# easyeda-schematics.net
KiCad netlist of a schematic drawn in EasyEDA
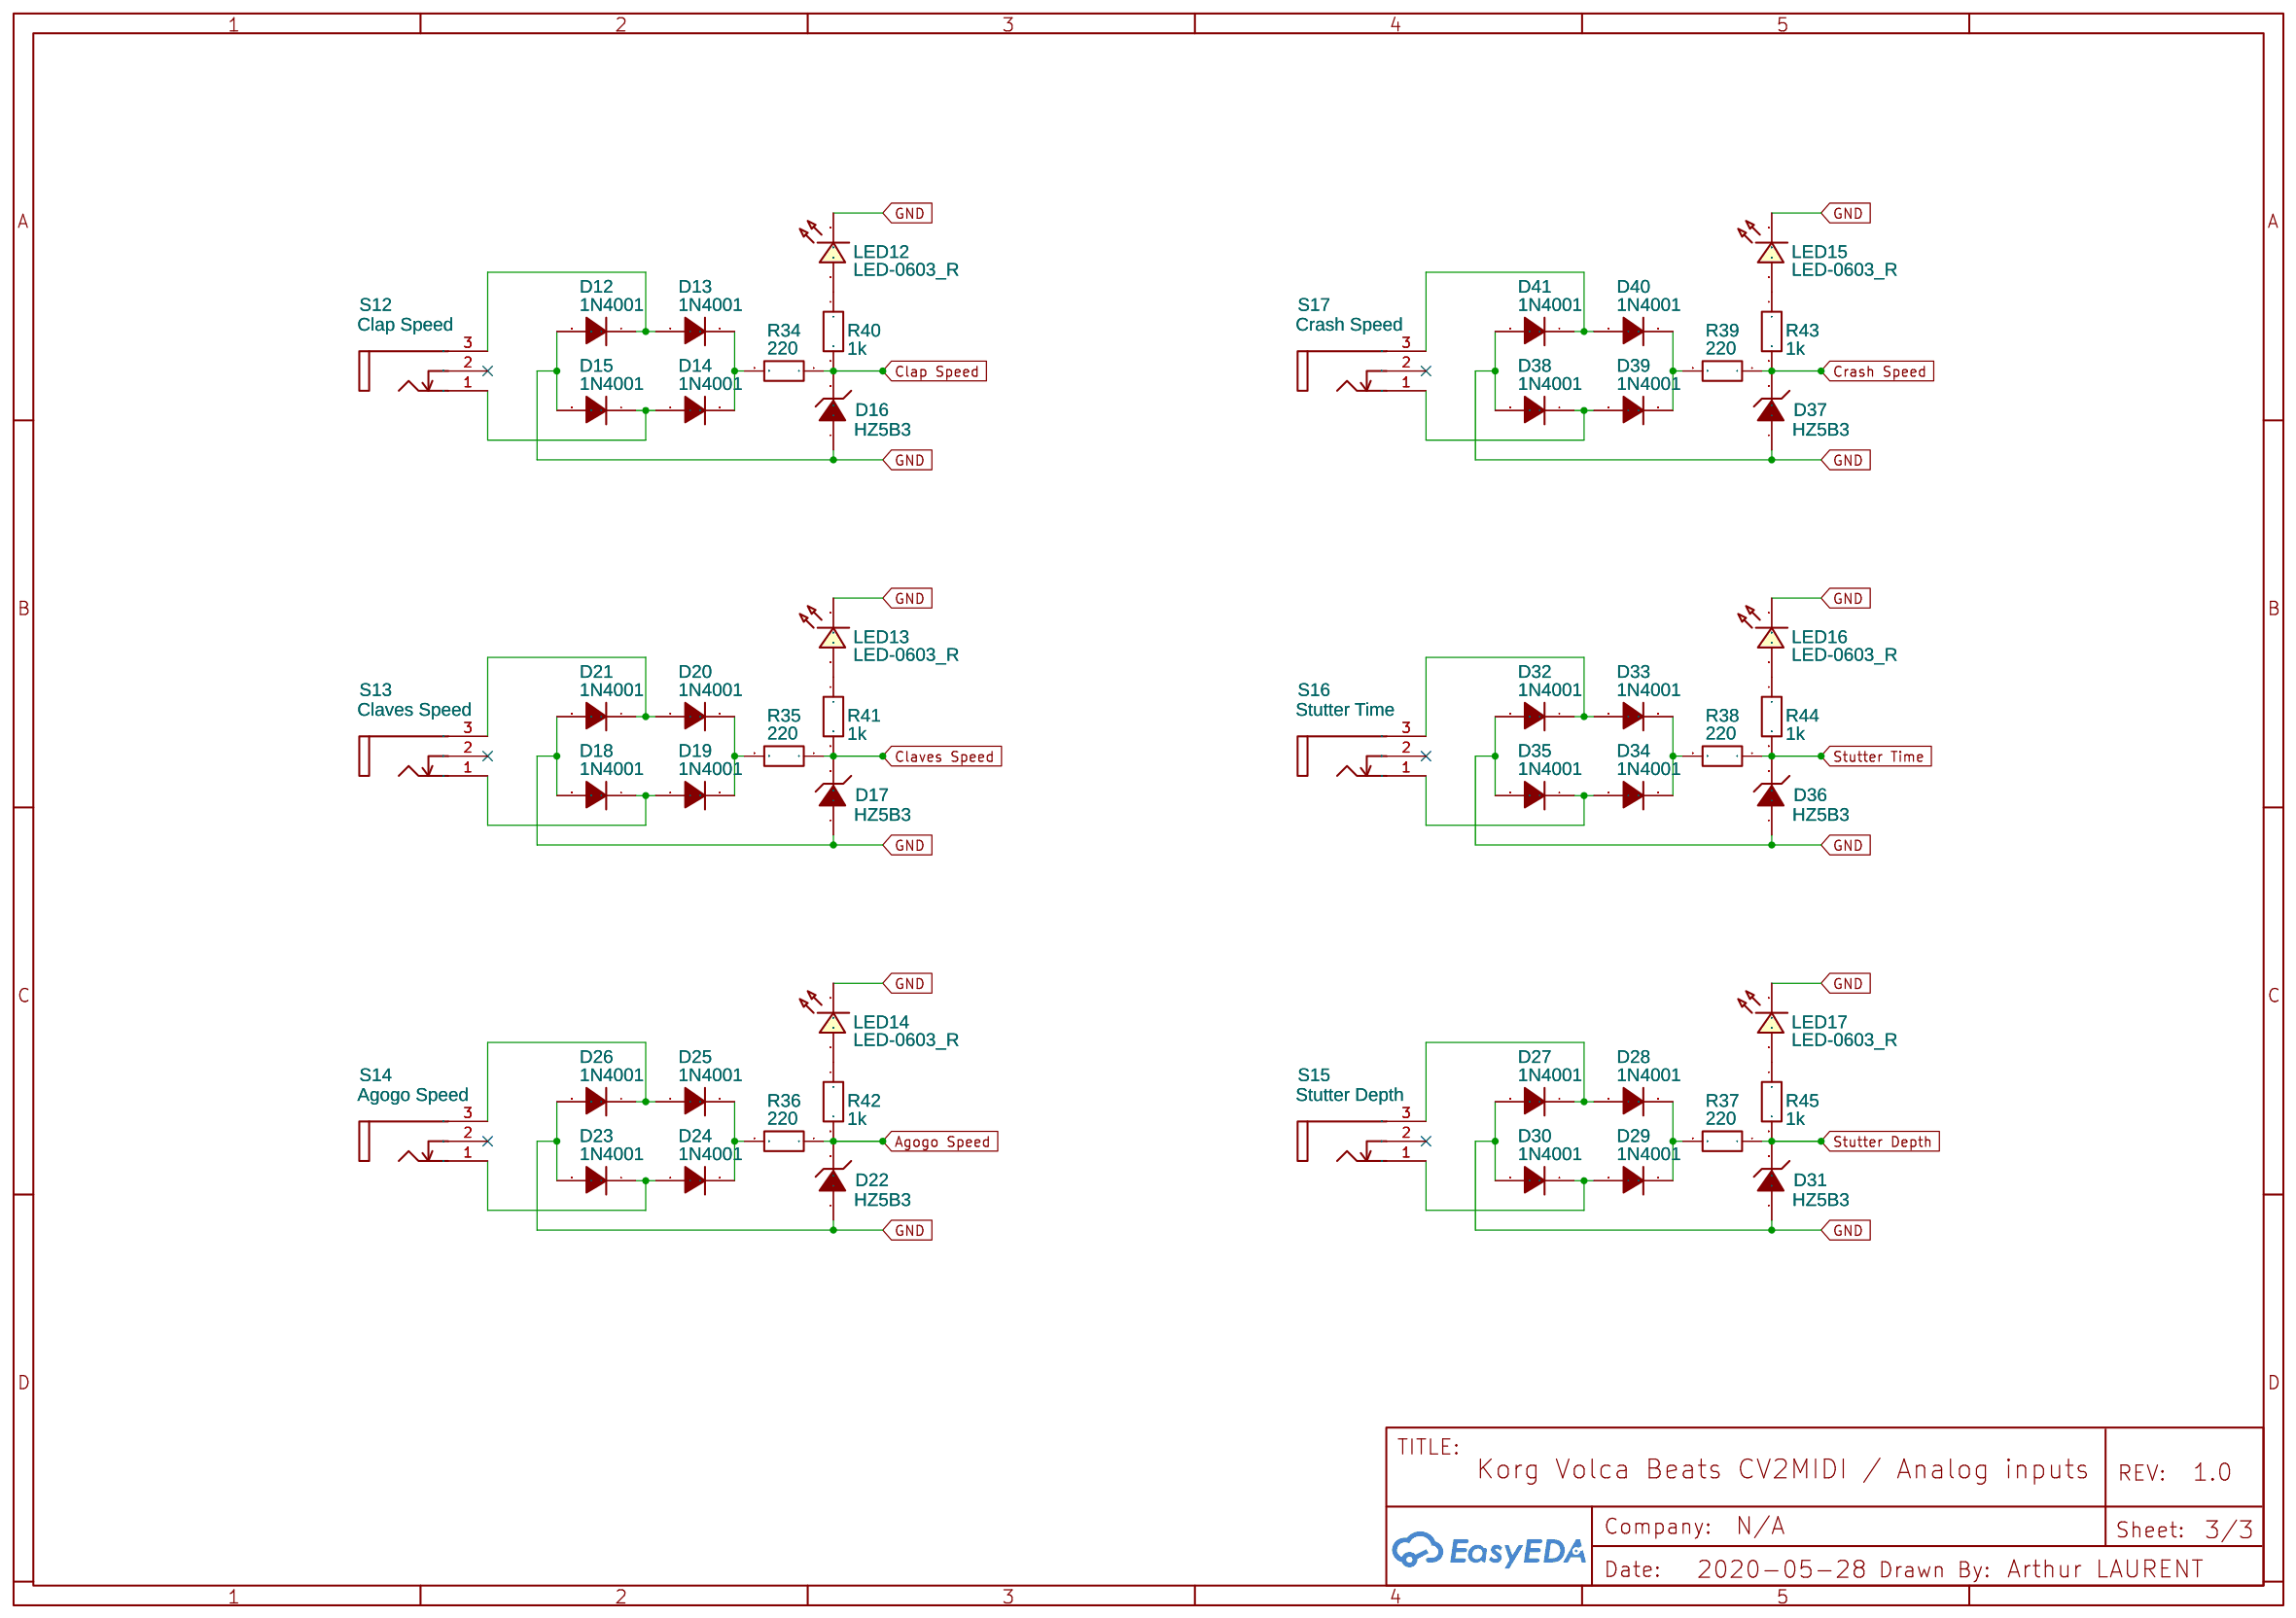
[diagram p0: Digital Inputs]
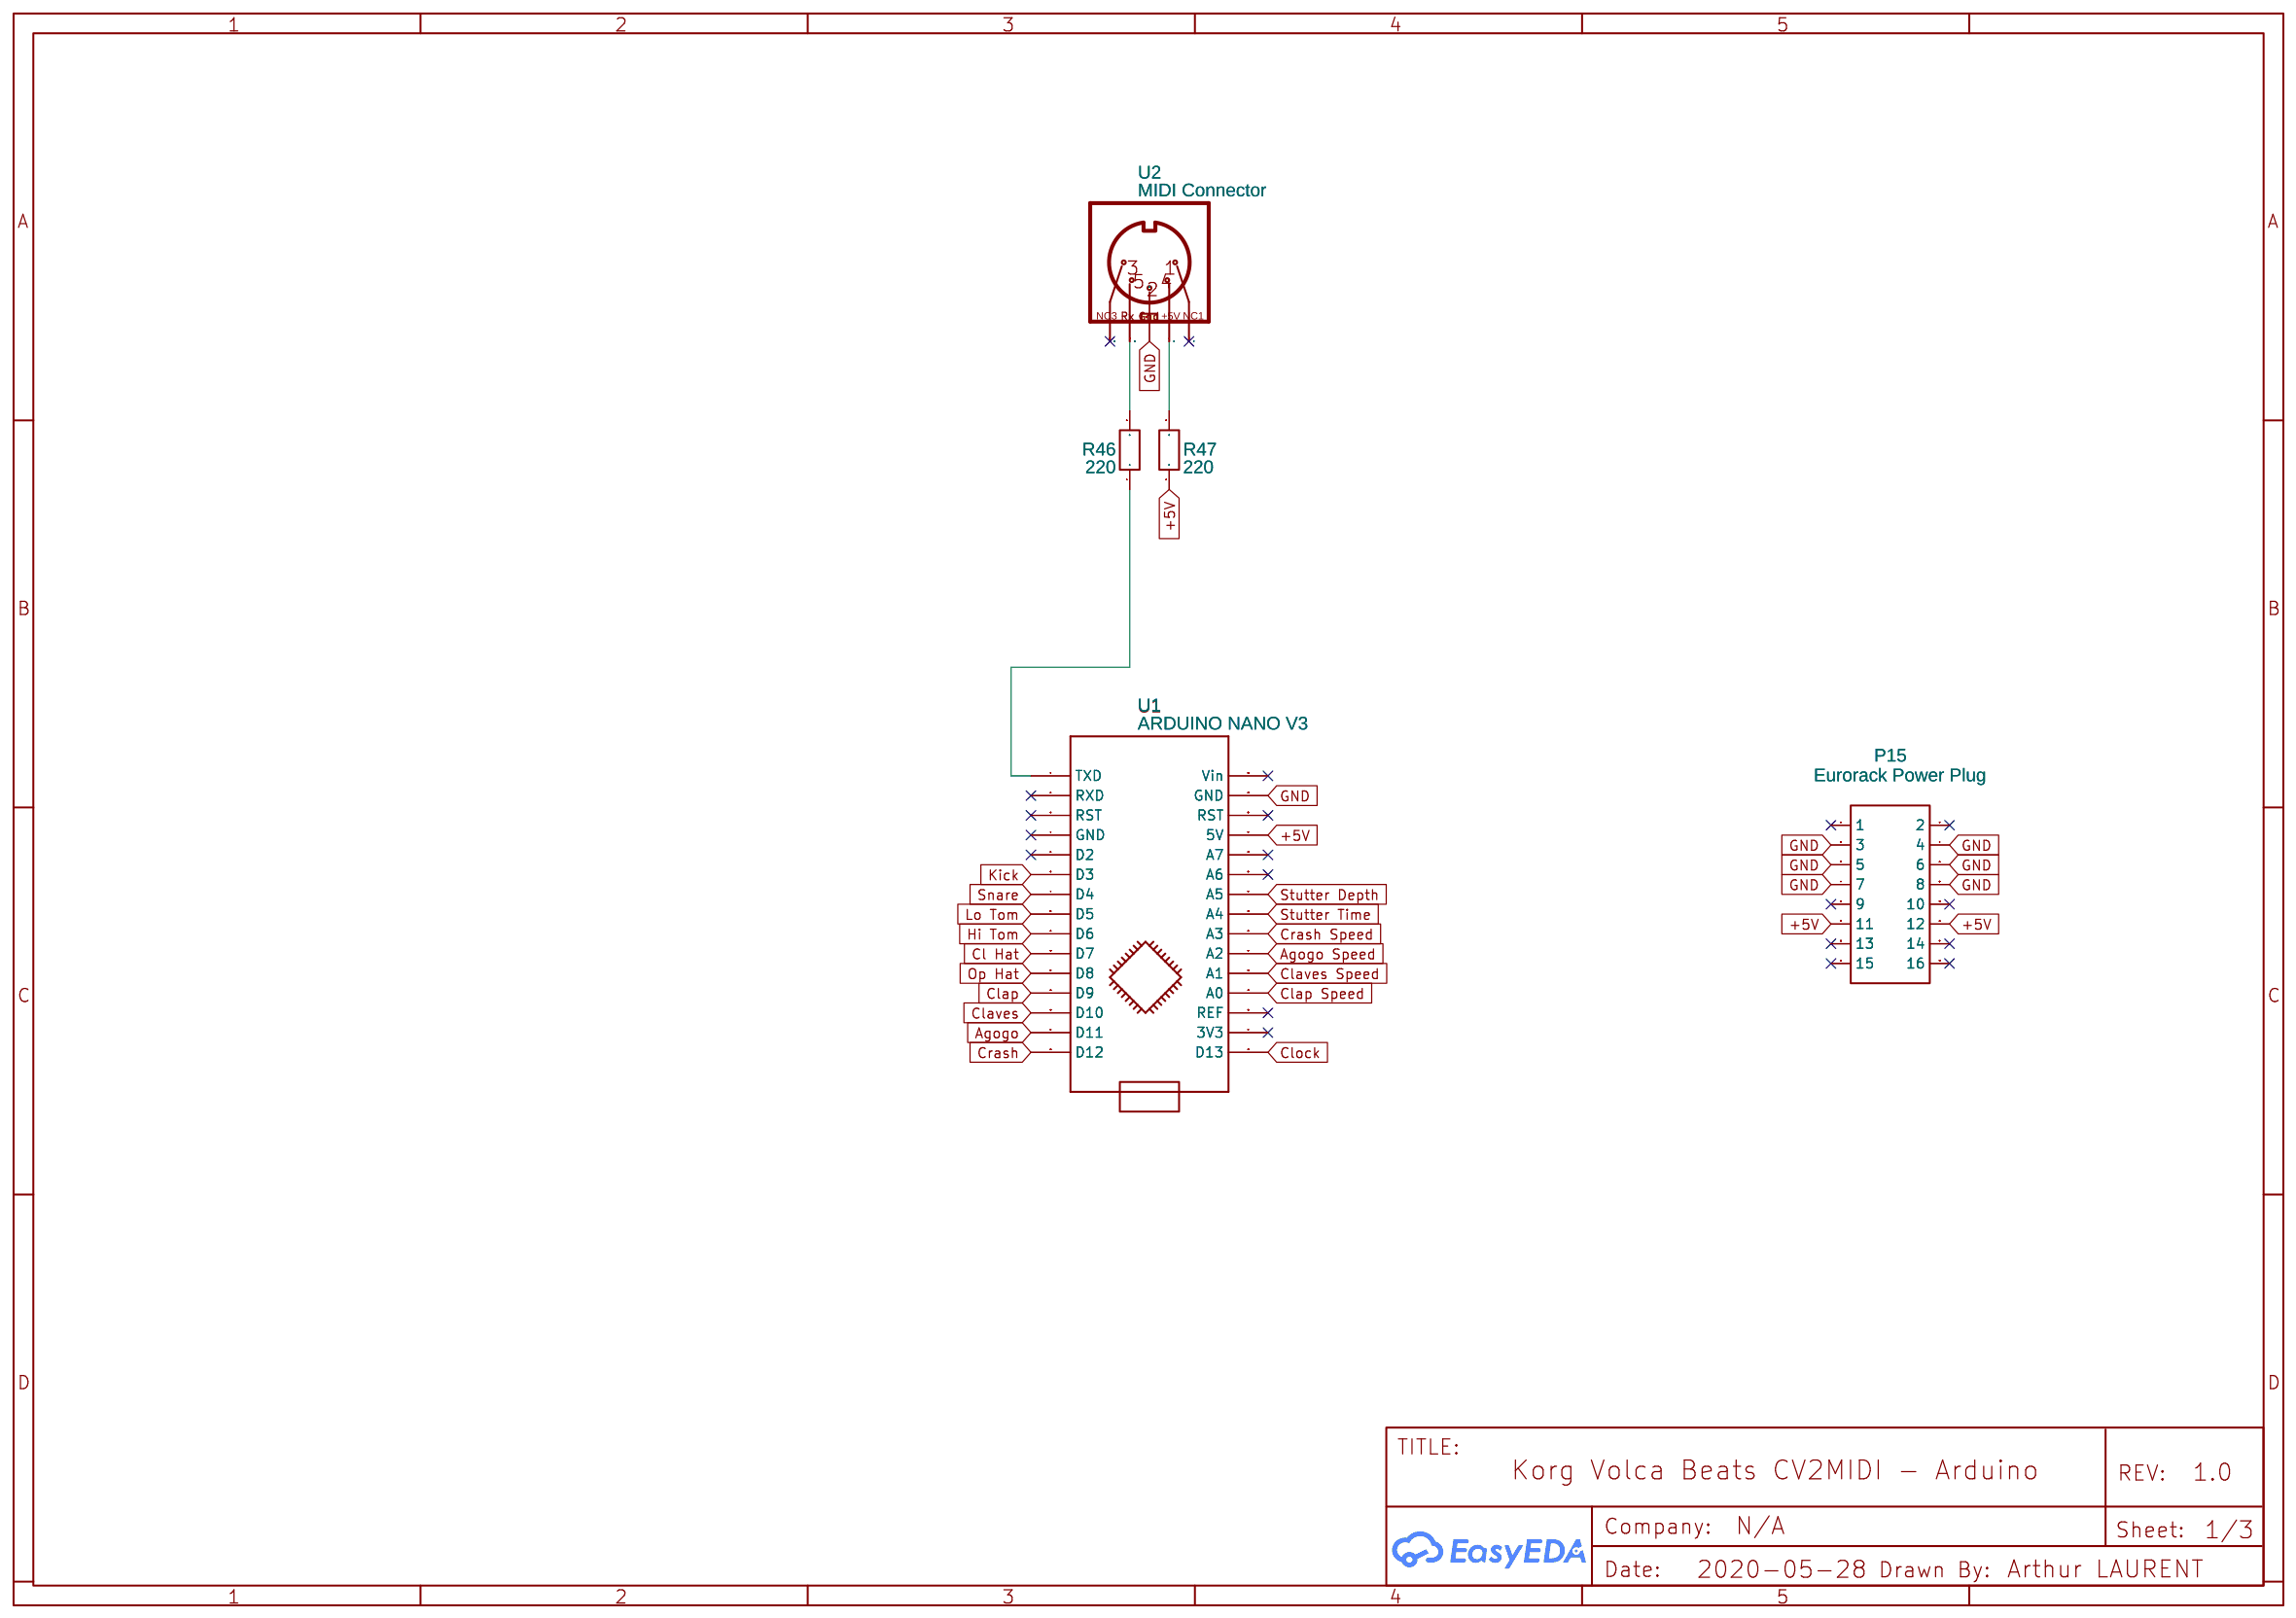
[diagram p1: Arduino]
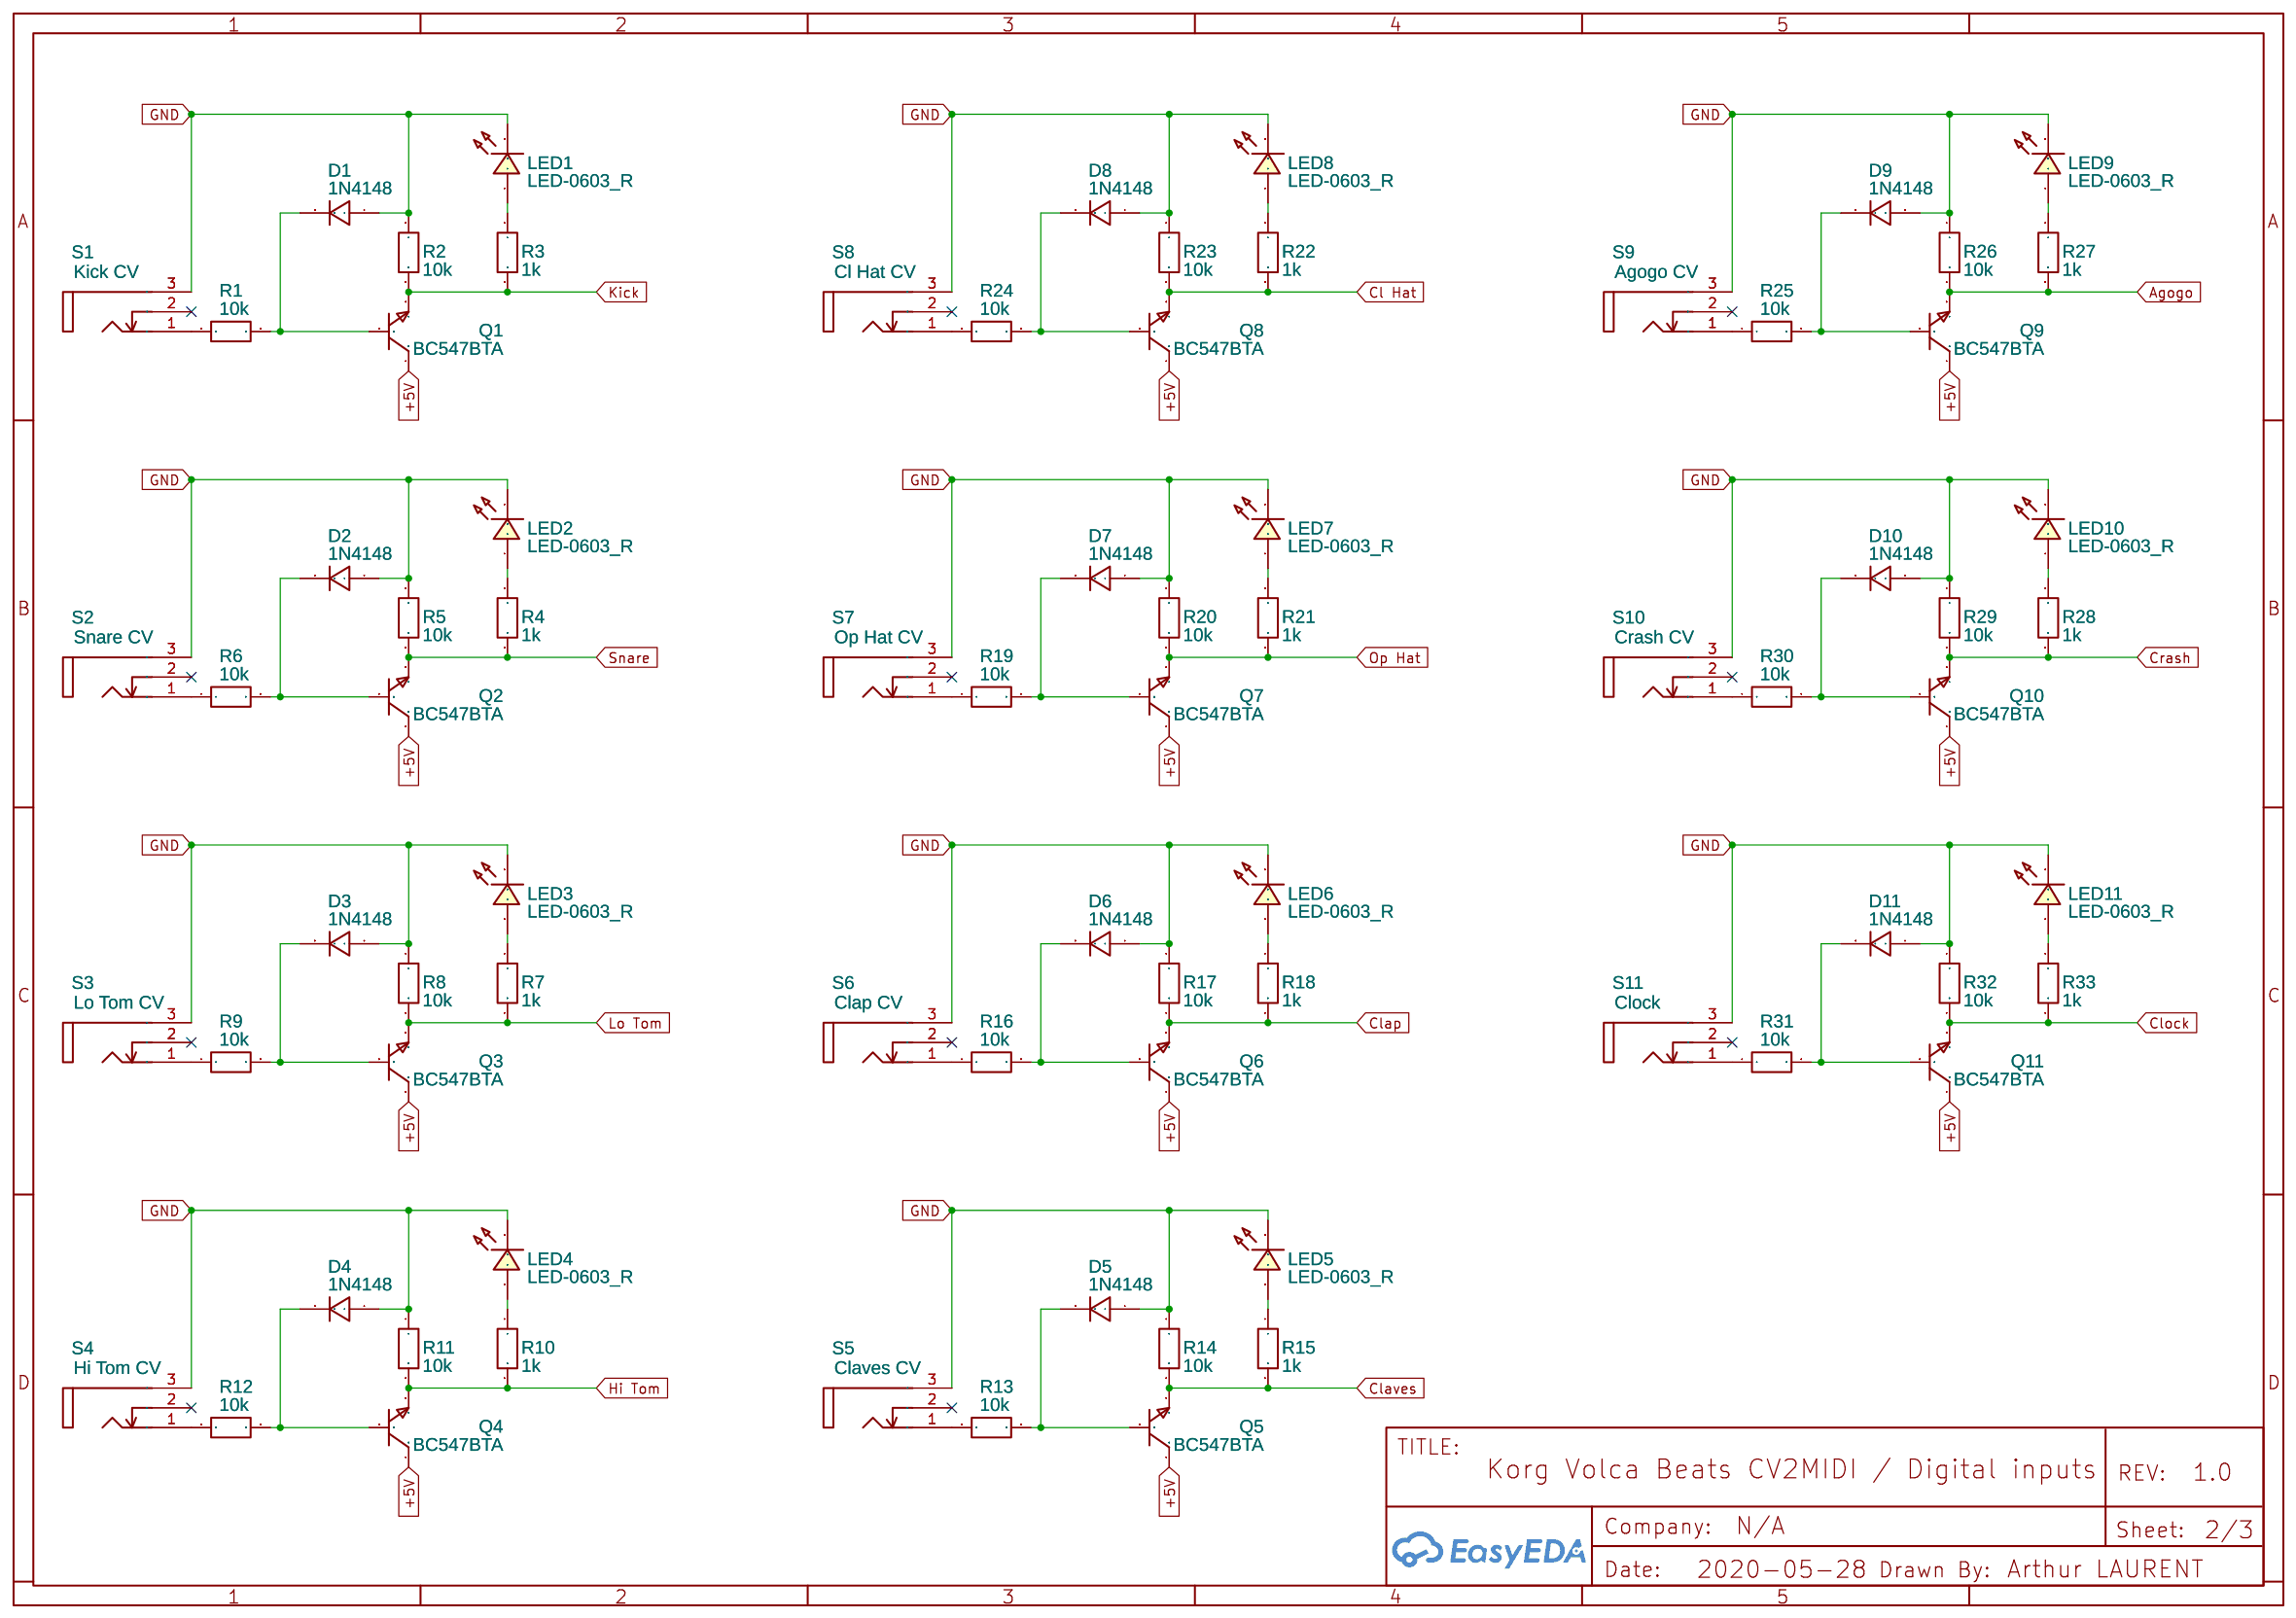
[diagram p2: Analog Inputs]

(export (version "E")
  (design (tool "Eeschema 10.0.6"))
  (components
    (comp (ref "D12")
      (value "1N4001")
      (fields (field (name "BOM_Supplier Part") "C82804"))
      (libsource (lib "") (part "1N4001"))
    )
    (comp (ref "D13")
      (value "1N4001")
      (fields (field (name "BOM_Supplier Part") "C82804"))
      (libsource (lib "") (part "1N4001"))
    )
    (comp (ref "D14")
      (value "1N4001")
      (fields (field (name "BOM_Supplier Part") "C82804"))
      (libsource (lib "") (part "1N4001"))
    )
    (comp (ref "D15")
      (value "1N4001")
      (fields (field (name "BOM_Supplier Part") "C82804"))
      (libsource (lib "") (part "1N4001"))
    )
    (comp (ref "D16")
      (value "HZ5B3")
      (fields (field (name "BOM_Supplier Part") "C45643"))
      (libsource (lib "") (part "HZ5B3"))
    )
    (comp (ref "D17")
      (value "HZ5B3")
      (fields (field (name "BOM_Supplier Part") "C45643"))
      (libsource (lib "") (part "HZ5B3"))
    )
    (comp (ref "D18")
      (value "1N4001")
      (fields (field (name "BOM_Supplier Part") "C82804"))
      (libsource (lib "") (part "1N4001"))
    )
    (comp (ref "D19")
      (value "1N4001")
      (fields (field (name "BOM_Supplier Part") "C82804"))
      (libsource (lib "") (part "1N4001"))
    )
    (comp (ref "D20")
      (value "1N4001")
      (fields (field (name "BOM_Supplier Part") "C82804"))
      (libsource (lib "") (part "1N4001"))
    )
    (comp (ref "D21")
      (value "1N4001")
      (fields (field (name "BOM_Supplier Part") "C82804"))
      (libsource (lib "") (part "1N4001"))
    )
    (comp (ref "D22")
      (value "HZ5B3")
      (fields (field (name "BOM_Supplier Part") "C45643"))
      (libsource (lib "") (part "HZ5B3"))
    )
    (comp (ref "D23")
      (value "1N4001")
      (fields (field (name "BOM_Supplier Part") "C82804"))
      (libsource (lib "") (part "1N4001"))
    )
    (comp (ref "D24")
      (value "1N4001")
      (fields (field (name "BOM_Supplier Part") "C82804"))
      (libsource (lib "") (part "1N4001"))
    )
    (comp (ref "D25")
      (value "1N4001")
      (fields (field (name "BOM_Supplier Part") "C82804"))
      (libsource (lib "") (part "1N4001"))
    )
    (comp (ref "D26")
      (value "1N4001")
      (fields (field (name "BOM_Supplier Part") "C82804"))
      (libsource (lib "") (part "1N4001"))
    )
    (comp (ref "D27")
      (value "1N4001")
      (fields (field (name "BOM_Supplier Part") "C82804"))
      (libsource (lib "") (part "1N4001"))
    )
    (comp (ref "D28")
      (value "1N4001")
      (fields (field (name "BOM_Supplier Part") "C82804"))
      (libsource (lib "") (part "1N4001"))
    )
    (comp (ref "D29")
      (value "1N4001")
      (fields (field (name "BOM_Supplier Part") "C82804"))
      (libsource (lib "") (part "1N4001"))
    )
    (comp (ref "D30")
      (value "1N4001")
      (fields (field (name "BOM_Supplier Part") "C82804"))
      (libsource (lib "") (part "1N4001"))
    )
    (comp (ref "D31")
      (value "HZ5B3")
      (fields (field (name "BOM_Supplier Part") "C45643"))
      (libsource (lib "") (part "HZ5B3"))
    )
    (comp (ref "D32")
      (value "1N4001")
      (fields (field (name "BOM_Supplier Part") "C82804"))
      (libsource (lib "") (part "1N4001"))
    )
    (comp (ref "D33")
      (value "1N4001")
      (fields (field (name "BOM_Supplier Part") "C82804"))
      (libsource (lib "") (part "1N4001"))
    )
    (comp (ref "D34")
      (value "1N4001")
      (fields (field (name "BOM_Supplier Part") "C82804"))
      (libsource (lib "") (part "1N4001"))
    )
    (comp (ref "D35")
      (value "1N4001")
      (fields (field (name "BOM_Supplier Part") "C82804"))
      (libsource (lib "") (part "1N4001"))
    )
    (comp (ref "D36")
      (value "HZ5B3")
      (fields (field (name "BOM_Supplier Part") "C45643"))
      (libsource (lib "") (part "HZ5B3"))
    )
    (comp (ref "D37")
      (value "HZ5B3")
      (fields (field (name "BOM_Supplier Part") "C45643"))
      (libsource (lib "") (part "HZ5B3"))
    )
    (comp (ref "D38")
      (value "1N4001")
      (fields (field (name "BOM_Supplier Part") "C82804"))
      (libsource (lib "") (part "1N4001"))
    )
    (comp (ref "D39")
      (value "1N4001")
      (fields (field (name "BOM_Supplier Part") "C82804"))
      (libsource (lib "") (part "1N4001"))
    )
    (comp (ref "D40")
      (value "1N4001")
      (fields (field (name "BOM_Supplier Part") "C82804"))
      (libsource (lib "") (part "1N4001"))
    )
    (comp (ref "D41")
      (value "1N4001")
      (fields (field (name "BOM_Supplier Part") "C82804"))
      (libsource (lib "") (part "1N4001"))
    )
    (comp (ref "LED12")
      (value "LED-0603_R")
      (fields
        (field (name "BOM_Manufacturer Part") "19-217/R6C-AL1M2VY/3T")
        (field (name "BOM_Supplier Part") "C72044")
      )
      (libsource (lib "") (part "LED-0603_R"))
    )
    (comp (ref "LED13")
      (value "LED-0603_R")
      (fields
        (field (name "BOM_Manufacturer Part") "19-217/R6C-AL1M2VY/3T")
        (field (name "BOM_Supplier Part") "C72044")
      )
      (libsource (lib "") (part "LED-0603_R"))
    )
    (comp (ref "LED14")
      (value "LED-0603_R")
      (fields
        (field (name "BOM_Manufacturer Part") "19-217/R6C-AL1M2VY/3T")
        (field (name "BOM_Supplier Part") "C72044")
      )
      (libsource (lib "") (part "LED-0603_R"))
    )
    (comp (ref "LED15")
      (value "LED-0603_R")
      (fields
        (field (name "BOM_Manufacturer Part") "19-217/R6C-AL1M2VY/3T")
        (field (name "BOM_Supplier Part") "C72044")
      )
      (libsource (lib "") (part "LED-0603_R"))
    )
    (comp (ref "LED16")
      (value "LED-0603_R")
      (fields
        (field (name "BOM_Manufacturer Part") "19-217/R6C-AL1M2VY/3T")
        (field (name "BOM_Supplier Part") "C72044")
      )
      (libsource (lib "") (part "LED-0603_R"))
    )
    (comp (ref "LED17")
      (value "LED-0603_R")
      (fields
        (field (name "BOM_Manufacturer Part") "19-217/R6C-AL1M2VY/3T")
        (field (name "BOM_Supplier Part") "C72044")
      )
      (libsource (lib "") (part "LED-0603_R"))
    )
    (comp (ref "R34") (value "220") (libsource (lib "") (part "R_0201_EU_1")))
    (comp (ref "R35") (value "220") (libsource (lib "") (part "R_0201_EU_1")))
    (comp (ref "R36") (value "220") (libsource (lib "") (part "R_0201_EU_1")))
    (comp (ref "R37") (value "220") (libsource (lib "") (part "R_0201_EU_1")))
    (comp (ref "R38") (value "220") (libsource (lib "") (part "R_0201_EU_1")))
    (comp (ref "R39") (value "220") (libsource (lib "") (part "R_0201_EU_1")))
    (comp (ref "R40") (value "1k") (libsource (lib "") (part "R_0201_EU")))
    (comp (ref "R41") (value "1k") (libsource (lib "") (part "R_0201_EU")))
    (comp (ref "R42") (value "1k") (libsource (lib "") (part "R_0201_EU")))
    (comp (ref "R43") (value "1k") (libsource (lib "") (part "R_0201_EU")))
    (comp (ref "R44") (value "1k") (libsource (lib "") (part "R_0201_EU")))
    (comp (ref "R45") (value "1k") (libsource (lib "") (part "R_0201_EU")))
    (comp (ref "S12") (value "Clap Speed") (libsource (lib "") (part "3.5mm Jack Socket Mono")))
    (comp (ref "S13") (value "Claves Speed") (libsource (lib "") (part "3.5mm Jack Socket Mono")))
    (comp (ref "S14") (value "Agogo Speed") (libsource (lib "") (part "3.5mm Jack Socket Mono")))
    (comp (ref "S15") (value "Stutter Depth") (libsource (lib "") (part "3.5mm Jack Socket Mono")))
    (comp (ref "S16") (value "Stutter Time") (libsource (lib "") (part "3.5mm Jack Socket Mono")))
    (comp (ref "S17") (value "Crash Speed") (libsource (lib "") (part "3.5mm Jack Socket Mono")))
    (comp (ref "P15")
      (value "Eurorack Power Plug")
      (fields
        (field (name "BOM_Manufacturer Part") "IDC Box 2.54mm 16P　Straight")
        (field (name "BOM_Supplier Part") "C3406")
      )
      (libsource (lib "") (part "HDR-IDC-2.54-2X8P"))
    )
    (comp (ref "R46") (value "220") (libsource (lib "") (part "R_0201_EU")))
    (comp (ref "R47") (value "220") (libsource (lib "") (part "R_0201_EU")))
    (comp (ref "U1")
      (value "ARDUINO NANO V3")
      (fields (field (name "BOM_Manufacturer Part") "arduino_nano1"))
      (libsource (lib "") (part "ARDUINO NANO V3"))
    )
    (comp (ref "U2") (value "MIDI Connector") (libsource (lib "") (part "MIDI Connector")))
    (comp (ref "D1") (value "1N4148") (libsource (lib "") (part "1N4148")))
    (comp (ref "D2") (value "1N4148") (libsource (lib "") (part "1N4148")))
    (comp (ref "D3") (value "1N4148") (libsource (lib "") (part "1N4148")))
    (comp (ref "D4") (value "1N4148") (libsource (lib "") (part "1N4148")))
    (comp (ref "D5") (value "1N4148") (libsource (lib "") (part "1N4148")))
    (comp (ref "D6") (value "1N4148") (libsource (lib "") (part "1N4148")))
    (comp (ref "D7") (value "1N4148") (libsource (lib "") (part "1N4148")))
    (comp (ref "D8") (value "1N4148") (libsource (lib "") (part "1N4148")))
    (comp (ref "D9") (value "1N4148") (libsource (lib "") (part "1N4148")))
    (comp (ref "D10") (value "1N4148") (libsource (lib "") (part "1N4148")))
    (comp (ref "D11") (value "1N4148") (libsource (lib "") (part "1N4148")))
    (comp (ref "LED1")
      (value "LED-0603_R")
      (fields
        (field (name "BOM_Manufacturer Part") "19-217/R6C-AL1M2VY/3T")
        (field (name "BOM_Supplier Part") "C72044")
      )
      (libsource (lib "") (part "LED-0603_R"))
    )
    (comp (ref "LED2")
      (value "LED-0603_R")
      (fields
        (field (name "BOM_Manufacturer Part") "19-217/R6C-AL1M2VY/3T")
        (field (name "BOM_Supplier Part") "C72044")
      )
      (libsource (lib "") (part "LED-0603_R"))
    )
    (comp (ref "LED3")
      (value "LED-0603_R")
      (fields
        (field (name "BOM_Manufacturer Part") "19-217/R6C-AL1M2VY/3T")
        (field (name "BOM_Supplier Part") "C72044")
      )
      (libsource (lib "") (part "LED-0603_R"))
    )
    (comp (ref "LED4")
      (value "LED-0603_R")
      (fields
        (field (name "BOM_Manufacturer Part") "19-217/R6C-AL1M2VY/3T")
        (field (name "BOM_Supplier Part") "C72044")
      )
      (libsource (lib "") (part "LED-0603_R"))
    )
    (comp (ref "LED5")
      (value "LED-0603_R")
      (fields
        (field (name "BOM_Manufacturer Part") "19-217/R6C-AL1M2VY/3T")
        (field (name "BOM_Supplier Part") "C72044")
      )
      (libsource (lib "") (part "LED-0603_R"))
    )
    (comp (ref "LED6")
      (value "LED-0603_R")
      (fields
        (field (name "BOM_Manufacturer Part") "19-217/R6C-AL1M2VY/3T")
        (field (name "BOM_Supplier Part") "C72044")
      )
      (libsource (lib "") (part "LED-0603_R"))
    )
    (comp (ref "LED7")
      (value "LED-0603_R")
      (fields
        (field (name "BOM_Manufacturer Part") "19-217/R6C-AL1M2VY/3T")
        (field (name "BOM_Supplier Part") "C72044")
      )
      (libsource (lib "") (part "LED-0603_R"))
    )
    (comp (ref "LED8")
      (value "LED-0603_R")
      (fields
        (field (name "BOM_Manufacturer Part") "19-217/R6C-AL1M2VY/3T")
        (field (name "BOM_Supplier Part") "C72044")
      )
      (libsource (lib "") (part "LED-0603_R"))
    )
    (comp (ref "LED9")
      (value "LED-0603_R")
      (fields
        (field (name "BOM_Manufacturer Part") "19-217/R6C-AL1M2VY/3T")
        (field (name "BOM_Supplier Part") "C72044")
      )
      (libsource (lib "") (part "LED-0603_R"))
    )
    (comp (ref "LED10")
      (value "LED-0603_R")
      (fields
        (field (name "BOM_Manufacturer Part") "19-217/R6C-AL1M2VY/3T")
        (field (name "BOM_Supplier Part") "C72044")
      )
      (libsource (lib "") (part "LED-0603_R"))
    )
    (comp (ref "LED11")
      (value "LED-0603_R")
      (fields
        (field (name "BOM_Manufacturer Part") "19-217/R6C-AL1M2VY/3T")
        (field (name "BOM_Supplier Part") "C72044")
      )
      (libsource (lib "") (part "LED-0603_R"))
    )
    (comp (ref "Q1")
      (value "BC547BTA")
      (fields (field (name "BOM_Supplier Part") "C258144"))
      (libsource (lib "") (part "BC547BTA"))
    )
    (comp (ref "Q2")
      (value "BC547BTA")
      (fields (field (name "BOM_Supplier Part") "C258144"))
      (libsource (lib "") (part "BC547BTA"))
    )
    (comp (ref "Q3")
      (value "BC547BTA")
      (fields (field (name "BOM_Supplier Part") "C258144"))
      (libsource (lib "") (part "BC547BTA"))
    )
    (comp (ref "Q4")
      (value "BC547BTA")
      (fields (field (name "BOM_Supplier Part") "C258144"))
      (libsource (lib "") (part "BC547BTA"))
    )
    (comp (ref "Q5")
      (value "BC547BTA")
      (fields (field (name "BOM_Supplier Part") "C258144"))
      (libsource (lib "") (part "BC547BTA"))
    )
    (comp (ref "Q6")
      (value "BC547BTA")
      (fields (field (name "BOM_Supplier Part") "C258144"))
      (libsource (lib "") (part "BC547BTA"))
    )
    (comp (ref "Q7")
      (value "BC547BTA")
      (fields (field (name "BOM_Supplier Part") "C258144"))
      (libsource (lib "") (part "BC547BTA"))
    )
    (comp (ref "Q8")
      (value "BC547BTA")
      (fields (field (name "BOM_Supplier Part") "C258144"))
      (libsource (lib "") (part "BC547BTA"))
    )
    (comp (ref "Q9")
      (value "BC547BTA")
      (fields (field (name "BOM_Supplier Part") "C258144"))
      (libsource (lib "") (part "BC547BTA"))
    )
    (comp (ref "Q10")
      (value "BC547BTA")
      (fields (field (name "BOM_Supplier Part") "C258144"))
      (libsource (lib "") (part "BC547BTA"))
    )
    (comp (ref "Q11")
      (value "BC547BTA")
      (fields (field (name "BOM_Supplier Part") "C258144"))
      (libsource (lib "") (part "BC547BTA"))
    )
    (comp (ref "R1") (value "10k") (libsource (lib "") (part "R_0201_EU_1")))
    (comp (ref "R2") (value "10k") (libsource (lib "") (part "R_0201_EU")))
    (comp (ref "R3") (value "1k") (libsource (lib "") (part "R_0201_EU")))
    (comp (ref "R4") (value "1k") (libsource (lib "") (part "R_0201_EU")))
    (comp (ref "R5") (value "10k") (libsource (lib "") (part "R_0201_EU")))
    (comp (ref "R6") (value "10k") (libsource (lib "") (part "R_0201_EU_1")))
    (comp (ref "R7") (value "1k") (libsource (lib "") (part "R_0201_EU")))
    (comp (ref "R8") (value "10k") (libsource (lib "") (part "R_0201_EU")))
    (comp (ref "R9") (value "10k") (libsource (lib "") (part "R_0201_EU_1")))
    (comp (ref "R10") (value "1k") (libsource (lib "") (part "R_0201_EU")))
    (comp (ref "R11") (value "10k") (libsource (lib "") (part "R_0201_EU")))
    (comp (ref "R12") (value "10k") (libsource (lib "") (part "R_0201_EU_1")))
    (comp (ref "R13") (value "10k") (libsource (lib "") (part "R_0201_EU_1")))
    (comp (ref "R14") (value "10k") (libsource (lib "") (part "R_0201_EU")))
    (comp (ref "R15") (value "1k") (libsource (lib "") (part "R_0201_EU")))
    (comp (ref "R16") (value "10k") (libsource (lib "") (part "R_0201_EU_1")))
    (comp (ref "R17") (value "10k") (libsource (lib "") (part "R_0201_EU")))
    (comp (ref "R18") (value "1k") (libsource (lib "") (part "R_0201_EU")))
    (comp (ref "R19") (value "10k") (libsource (lib "") (part "R_0201_EU_1")))
    (comp (ref "R20") (value "10k") (libsource (lib "") (part "R_0201_EU")))
    (comp (ref "R21") (value "1k") (libsource (lib "") (part "R_0201_EU")))
    (comp (ref "R22") (value "1k") (libsource (lib "") (part "R_0201_EU")))
    (comp (ref "R23") (value "10k") (libsource (lib "") (part "R_0201_EU")))
    (comp (ref "R24") (value "10k") (libsource (lib "") (part "R_0201_EU_1")))
    (comp (ref "R25") (value "10k") (libsource (lib "") (part "R_0201_EU_1")))
    (comp (ref "R26") (value "10k") (libsource (lib "") (part "R_0201_EU")))
    (comp (ref "R27") (value "1k") (libsource (lib "") (part "R_0201_EU")))
    (comp (ref "R28") (value "1k") (libsource (lib "") (part "R_0201_EU")))
    (comp (ref "R29") (value "10k") (libsource (lib "") (part "R_0201_EU")))
    (comp (ref "R30") (value "10k") (libsource (lib "") (part "R_0201_EU_1")))
    (comp (ref "R31") (value "10k") (libsource (lib "") (part "R_0201_EU_1")))
    (comp (ref "R32") (value "10k") (libsource (lib "") (part "R_0201_EU")))
    (comp (ref "R33") (value "1k") (libsource (lib "") (part "R_0201_EU")))
    (comp (ref "S1") (value "Kick CV") (libsource (lib "") (part "3.5mm Jack Socket Mono")))
    (comp (ref "S2") (value "Snare CV") (libsource (lib "") (part "3.5mm Jack Socket Mono")))
    (comp (ref "S3") (value "Lo Tom CV") (libsource (lib "") (part "3.5mm Jack Socket Mono")))
    (comp (ref "S4") (value "Hi Tom CV") (libsource (lib "") (part "3.5mm Jack Socket Mono")))
    (comp (ref "S5") (value "Claves CV") (libsource (lib "") (part "3.5mm Jack Socket Mono")))
    (comp (ref "S6") (value "Clap CV") (libsource (lib "") (part "3.5mm Jack Socket Mono")))
    (comp (ref "S7") (value "Op Hat CV") (libsource (lib "") (part "3.5mm Jack Socket Mono")))
    (comp (ref "S8") (value "Cl Hat CV") (libsource (lib "") (part "3.5mm Jack Socket Mono")))
    (comp (ref "S9") (value "Agogo CV") (libsource (lib "") (part "3.5mm Jack Socket Mono")))
    (comp (ref "S10") (value "Crash CV") (libsource (lib "") (part "3.5mm Jack Socket Mono")))
    (comp (ref "S11") (value "Clock") (libsource (lib "") (part "3.5mm Jack Socket Mono")))
  )
  (nets
    (net (code "1") (name "+5V") (class "Default")
      (node (ref "P15") (pin "11") (pinfunction "11_11") (pintype "unspecified"))
      (node (ref "P15") (pin "12") (pinfunction "12_12") (pintype "unspecified"))
      (node (ref "Q1") (pin "1") (pinfunction "C_1") (pintype "unspecified"))
      (node (ref "Q10") (pin "1") (pinfunction "C_1") (pintype "unspecified"))
      (node (ref "Q11") (pin "1") (pinfunction "C_1") (pintype "unspecified"))
      (node (ref "Q2") (pin "1") (pinfunction "C_1") (pintype "unspecified"))
      (node (ref "Q3") (pin "1") (pinfunction "C_1") (pintype "unspecified"))
      (node (ref "Q4") (pin "1") (pinfunction "C_1") (pintype "unspecified"))
      (node (ref "Q5") (pin "1") (pinfunction "C_1") (pintype "unspecified"))
      (node (ref "Q6") (pin "1") (pinfunction "C_1") (pintype "unspecified"))
      (node (ref "Q7") (pin "1") (pinfunction "C_1") (pintype "unspecified"))
      (node (ref "Q8") (pin "1") (pinfunction "C_1") (pintype "unspecified"))
      (node (ref "Q9") (pin "1") (pinfunction "C_1") (pintype "unspecified"))
      (node (ref "R47") (pin "1") (pinfunction "1_1") (pintype "unspecified"))
      (node (ref "U1") (pin "27") (pinfunction "5V_27") (pintype "output"))
    )
    (net (code "2") (name "Agogo") (class "Default")
      (node (ref "Q9") (pin "3") (pinfunction "E_3") (pintype "unspecified"))
      (node (ref "R26") (pin "2") (pinfunction "2_2") (pintype "unspecified"))
      (node (ref "R27") (pin "2") (pinfunction "2_2") (pintype "unspecified"))
      (node (ref "U1") (pin "14") (pinfunction "D11_14") (pintype "unspecified"))
    )
    (net (code "3") (name "Agogo Speed") (class "Default")
      (node (ref "D22") (pin "2") (pinfunction "K_2") (pintype "unspecified"))
      (node (ref "R36") (pin "1") (pinfunction "1_1") (pintype "unspecified"))
      (node (ref "R42") (pin "2") (pinfunction "2_2") (pintype "unspecified"))
      (node (ref "U1") (pin "21") (pinfunction "A2_21") (pintype "unspecified"))
    )
    (net (code "4") (name "Cl Hat") (class "Default")
      (node (ref "Q8") (pin "3") (pinfunction "E_3") (pintype "unspecified"))
      (node (ref "R22") (pin "2") (pinfunction "2_2") (pintype "unspecified"))
      (node (ref "R23") (pin "2") (pinfunction "2_2") (pintype "unspecified"))
      (node (ref "U1") (pin "10") (pinfunction "D7_10") (pintype "unspecified"))
    )
    (net (code "5") (name "Clap") (class "Default")
      (node (ref "Q6") (pin "3") (pinfunction "E_3") (pintype "unspecified"))
      (node (ref "R17") (pin "2") (pinfunction "2_2") (pintype "unspecified"))
      (node (ref "R18") (pin "2") (pinfunction "2_2") (pintype "unspecified"))
      (node (ref "U1") (pin "12") (pinfunction "D9_12") (pintype "unspecified"))
    )
    (net (code "6") (name "Clap Speed") (class "Default")
      (node (ref "D16") (pin "2") (pinfunction "K_2") (pintype "unspecified"))
      (node (ref "R34") (pin "1") (pinfunction "1_1") (pintype "unspecified"))
      (node (ref "R40") (pin "2") (pinfunction "2_2") (pintype "unspecified"))
      (node (ref "U1") (pin "19") (pinfunction "A0_19") (pintype "unspecified"))
    )
    (net (code "7") (name "Claves") (class "Default")
      (node (ref "Q5") (pin "3") (pinfunction "E_3") (pintype "unspecified"))
      (node (ref "R14") (pin "2") (pinfunction "2_2") (pintype "unspecified"))
      (node (ref "R15") (pin "2") (pinfunction "2_2") (pintype "unspecified"))
      (node (ref "U1") (pin "13") (pinfunction "D10_13") (pintype "unspecified"))
    )
    (net (code "8") (name "Claves Speed") (class "Default")
      (node (ref "D17") (pin "2") (pinfunction "K_2") (pintype "unspecified"))
      (node (ref "R35") (pin "1") (pinfunction "1_1") (pintype "unspecified"))
      (node (ref "R41") (pin "2") (pinfunction "2_2") (pintype "unspecified"))
      (node (ref "U1") (pin "20") (pinfunction "A1_20") (pintype "unspecified"))
    )
    (net (code "9") (name "Clock") (class "Default")
      (node (ref "Q11") (pin "3") (pinfunction "E_3") (pintype "unspecified"))
      (node (ref "R32") (pin "2") (pinfunction "2_2") (pintype "unspecified"))
      (node (ref "R33") (pin "2") (pinfunction "2_2") (pintype "unspecified"))
      (node (ref "U1") (pin "16") (pinfunction "D13_16") (pintype "unspecified"))
    )
    (net (code "10") (name "Crash") (class "Default")
      (node (ref "Q10") (pin "3") (pinfunction "E_3") (pintype "unspecified"))
      (node (ref "R28") (pin "2") (pinfunction "2_2") (pintype "unspecified"))
      (node (ref "R29") (pin "2") (pinfunction "2_2") (pintype "unspecified"))
      (node (ref "U1") (pin "15") (pinfunction "D12_15") (pintype "unspecified"))
    )
    (net (code "11") (name "Crash Speed") (class "Default")
      (node (ref "D37") (pin "2") (pinfunction "K_2") (pintype "unspecified"))
      (node (ref "R39") (pin "1") (pinfunction "1_1") (pintype "unspecified"))
      (node (ref "R43") (pin "2") (pinfunction "2_2") (pintype "unspecified"))
      (node (ref "U1") (pin "22") (pinfunction "A3_22") (pintype "unspecified"))
    )
    (net (code "12") (name "GND") (class "Default")
      (node (ref "D1") (pin "1") (pinfunction "A_1") (pintype "unspecified"))
      (node (ref "D10") (pin "1") (pinfunction "A_1") (pintype "unspecified"))
      (node (ref "D11") (pin "1") (pinfunction "A_1") (pintype "unspecified"))
      (node (ref "D12") (pin "2") (pinfunction "A_2") (pintype "unspecified"))
      (node (ref "D15") (pin "2") (pinfunction "A_2") (pintype "unspecified"))
      (node (ref "D16") (pin "1") (pinfunction "A_1") (pintype "unspecified"))
      (node (ref "D17") (pin "1") (pinfunction "A_1") (pintype "unspecified"))
      (node (ref "D18") (pin "2") (pinfunction "A_2") (pintype "unspecified"))
      (node (ref "D2") (pin "1") (pinfunction "A_1") (pintype "unspecified"))
      (node (ref "D21") (pin "2") (pinfunction "A_2") (pintype "unspecified"))
      (node (ref "D22") (pin "1") (pinfunction "A_1") (pintype "unspecified"))
      (node (ref "D23") (pin "2") (pinfunction "A_2") (pintype "unspecified"))
      (node (ref "D26") (pin "2") (pinfunction "A_2") (pintype "unspecified"))
      (node (ref "D27") (pin "2") (pinfunction "A_2") (pintype "unspecified"))
      (node (ref "D3") (pin "1") (pinfunction "A_1") (pintype "unspecified"))
      (node (ref "D30") (pin "2") (pinfunction "A_2") (pintype "unspecified"))
      (node (ref "D31") (pin "1") (pinfunction "A_1") (pintype "unspecified"))
      (node (ref "D32") (pin "2") (pinfunction "A_2") (pintype "unspecified"))
      (node (ref "D35") (pin "2") (pinfunction "A_2") (pintype "unspecified"))
      (node (ref "D36") (pin "1") (pinfunction "A_1") (pintype "unspecified"))
      (node (ref "D37") (pin "1") (pinfunction "A_1") (pintype "unspecified"))
      (node (ref "D38") (pin "2") (pinfunction "A_2") (pintype "unspecified"))
      (node (ref "D4") (pin "1") (pinfunction "A_1") (pintype "unspecified"))
      (node (ref "D41") (pin "2") (pinfunction "A_2") (pintype "unspecified"))
      (node (ref "D5") (pin "1") (pinfunction "A_1") (pintype "unspecified"))
      (node (ref "D6") (pin "1") (pinfunction "A_1") (pintype "unspecified"))
      (node (ref "D7") (pin "1") (pinfunction "A_1") (pintype "unspecified"))
      (node (ref "D8") (pin "1") (pinfunction "A_1") (pintype "unspecified"))
      (node (ref "D9") (pin "1") (pinfunction "A_1") (pintype "unspecified"))
      (node (ref "LED1") (pin "2") (pinfunction "2_2") (pintype "unspecified"))
      (node (ref "LED10") (pin "2") (pinfunction "2_2") (pintype "unspecified"))
      (node (ref "LED11") (pin "2") (pinfunction "2_2") (pintype "unspecified"))
      (node (ref "LED12") (pin "2") (pinfunction "2_2") (pintype "unspecified"))
      (node (ref "LED13") (pin "2") (pinfunction "2_2") (pintype "unspecified"))
      (node (ref "LED14") (pin "2") (pinfunction "2_2") (pintype "unspecified"))
      (node (ref "LED15") (pin "2") (pinfunction "2_2") (pintype "unspecified"))
      (node (ref "LED16") (pin "2") (pinfunction "2_2") (pintype "unspecified"))
      (node (ref "LED17") (pin "2") (pinfunction "2_2") (pintype "unspecified"))
      (node (ref "LED2") (pin "2") (pinfunction "2_2") (pintype "unspecified"))
      (node (ref "LED3") (pin "2") (pinfunction "2_2") (pintype "unspecified"))
      (node (ref "LED4") (pin "2") (pinfunction "2_2") (pintype "unspecified"))
      (node (ref "LED5") (pin "2") (pinfunction "2_2") (pintype "unspecified"))
      (node (ref "LED6") (pin "2") (pinfunction "2_2") (pintype "unspecified"))
      (node (ref "LED7") (pin "2") (pinfunction "2_2") (pintype "unspecified"))
      (node (ref "LED8") (pin "2") (pinfunction "2_2") (pintype "unspecified"))
      (node (ref "LED9") (pin "2") (pinfunction "2_2") (pintype "unspecified"))
      (node (ref "P15") (pin "3") (pinfunction "3_3") (pintype "unspecified"))
      (node (ref "P15") (pin "4") (pinfunction "4_4") (pintype "unspecified"))
      (node (ref "P15") (pin "5") (pinfunction "5_5") (pintype "unspecified"))
      (node (ref "P15") (pin "6") (pinfunction "6_6") (pintype "unspecified"))
      (node (ref "P15") (pin "7") (pinfunction "7_7") (pintype "unspecified"))
      (node (ref "P15") (pin "8") (pinfunction "8_8") (pintype "unspecified"))
      (node (ref "R11") (pin "1") (pinfunction "1_1") (pintype "unspecified"))
      (node (ref "R14") (pin "1") (pinfunction "1_1") (pintype "unspecified"))
      (node (ref "R17") (pin "1") (pinfunction "1_1") (pintype "unspecified"))
      (node (ref "R2") (pin "1") (pinfunction "1_1") (pintype "unspecified"))
      (node (ref "R20") (pin "1") (pinfunction "1_1") (pintype "unspecified"))
      (node (ref "R23") (pin "1") (pinfunction "1_1") (pintype "unspecified"))
      (node (ref "R26") (pin "1") (pinfunction "1_1") (pintype "unspecified"))
      (node (ref "R29") (pin "1") (pinfunction "1_1") (pintype "unspecified"))
      (node (ref "R32") (pin "1") (pinfunction "1_1") (pintype "unspecified"))
      (node (ref "R5") (pin "1") (pinfunction "1_1") (pintype "unspecified"))
      (node (ref "R8") (pin "1") (pinfunction "1_1") (pintype "unspecified"))
      (node (ref "S1") (pin "3") (pinfunction "1_3") (pintype "unspecified"))
      (node (ref "S10") (pin "3") (pinfunction "1_3") (pintype "unspecified"))
      (node (ref "S11") (pin "3") (pinfunction "1_3") (pintype "unspecified"))
      (node (ref "S2") (pin "3") (pinfunction "1_3") (pintype "unspecified"))
      (node (ref "S3") (pin "3") (pinfunction "1_3") (pintype "unspecified"))
      (node (ref "S4") (pin "3") (pinfunction "1_3") (pintype "unspecified"))
      (node (ref "S5") (pin "3") (pinfunction "1_3") (pintype "unspecified"))
      (node (ref "S6") (pin "3") (pinfunction "1_3") (pintype "unspecified"))
      (node (ref "S7") (pin "3") (pinfunction "1_3") (pintype "unspecified"))
      (node (ref "S8") (pin "3") (pinfunction "1_3") (pintype "unspecified"))
      (node (ref "S9") (pin "3") (pinfunction "1_3") (pintype "unspecified"))
      (node (ref "U1") (pin "29") (pinfunction "GND_29") (pintype "unspecified"))
      (node (ref "U2") (pin "2") (pinfunction "2_2") (pintype "unspecified"))
    )
    (net (code "13") (name "Hi Tom") (class "Default")
      (node (ref "Q4") (pin "3") (pinfunction "E_3") (pintype "unspecified"))
      (node (ref "R10") (pin "2") (pinfunction "2_2") (pintype "unspecified"))
      (node (ref "R11") (pin "2") (pinfunction "2_2") (pintype "unspecified"))
      (node (ref "U1") (pin "9") (pinfunction "D6_9") (pintype "unspecified"))
    )
    (net (code "14") (name "Kick") (class "Default")
      (node (ref "Q1") (pin "3") (pinfunction "E_3") (pintype "unspecified"))
      (node (ref "R2") (pin "2") (pinfunction "2_2") (pintype "unspecified"))
      (node (ref "R3") (pin "2") (pinfunction "2_2") (pintype "unspecified"))
      (node (ref "U1") (pin "6") (pinfunction "D3_6") (pintype "unspecified"))
    )
    (net (code "15") (name "Lo Tom") (class "Default")
      (node (ref "Q3") (pin "3") (pinfunction "E_3") (pintype "unspecified"))
      (node (ref "R7") (pin "2") (pinfunction "2_2") (pintype "unspecified"))
      (node (ref "R8") (pin "2") (pinfunction "2_2") (pintype "unspecified"))
      (node (ref "U1") (pin "8") (pinfunction "D5_8") (pintype "unspecified"))
    )
    (net (code "16") (name "Net-(D1-K)") (class "Default")
      (node (ref "D1") (pin "2") (pinfunction "K_2") (pintype "unspecified"))
      (node (ref "Q1") (pin "2") (pinfunction "B_2") (pintype "unspecified"))
      (node (ref "R1") (pin "2") (pinfunction "2_2") (pintype "unspecified"))
    )
    (net (code "17") (name "Net-(D2-K)") (class "Default")
      (node (ref "D2") (pin "2") (pinfunction "K_2") (pintype "unspecified"))
      (node (ref "Q2") (pin "2") (pinfunction "B_2") (pintype "unspecified"))
      (node (ref "R6") (pin "2") (pinfunction "2_2") (pintype "unspecified"))
    )
    (net (code "18") (name "Net-(D3-K)") (class "Default")
      (node (ref "D3") (pin "2") (pinfunction "K_2") (pintype "unspecified"))
      (node (ref "Q3") (pin "2") (pinfunction "B_2") (pintype "unspecified"))
      (node (ref "R9") (pin "2") (pinfunction "2_2") (pintype "unspecified"))
    )
    (net (code "19") (name "Net-(D4-K)") (class "Default")
      (node (ref "D4") (pin "2") (pinfunction "K_2") (pintype "unspecified"))
      (node (ref "Q4") (pin "2") (pinfunction "B_2") (pintype "unspecified"))
      (node (ref "R12") (pin "2") (pinfunction "2_2") (pintype "unspecified"))
    )
    (net (code "20") (name "Net-(D5-K)") (class "Default")
      (node (ref "D5") (pin "2") (pinfunction "K_2") (pintype "unspecified"))
      (node (ref "Q5") (pin "2") (pinfunction "B_2") (pintype "unspecified"))
      (node (ref "R13") (pin "2") (pinfunction "2_2") (pintype "unspecified"))
    )
    (net (code "21") (name "Net-(D6-K)") (class "Default")
      (node (ref "D6") (pin "2") (pinfunction "K_2") (pintype "unspecified"))
      (node (ref "Q6") (pin "2") (pinfunction "B_2") (pintype "unspecified"))
      (node (ref "R16") (pin "2") (pinfunction "2_2") (pintype "unspecified"))
    )
    (net (code "22") (name "Net-(D7-K)") (class "Default")
      (node (ref "D7") (pin "2") (pinfunction "K_2") (pintype "unspecified"))
      (node (ref "Q7") (pin "2") (pinfunction "B_2") (pintype "unspecified"))
      (node (ref "R19") (pin "2") (pinfunction "2_2") (pintype "unspecified"))
    )
    (net (code "23") (name "Net-(D8-K)") (class "Default")
      (node (ref "D8") (pin "2") (pinfunction "K_2") (pintype "unspecified"))
      (node (ref "Q8") (pin "2") (pinfunction "B_2") (pintype "unspecified"))
      (node (ref "R24") (pin "2") (pinfunction "2_2") (pintype "unspecified"))
    )
    (net (code "24") (name "Net-(D9-K)") (class "Default")
      (node (ref "D9") (pin "2") (pinfunction "K_2") (pintype "unspecified"))
      (node (ref "Q9") (pin "2") (pinfunction "B_2") (pintype "unspecified"))
      (node (ref "R25") (pin "2") (pinfunction "2_2") (pintype "unspecified"))
    )
    (net (code "25") (name "Net-(D10-K)") (class "Default")
      (node (ref "D10") (pin "2") (pinfunction "K_2") (pintype "unspecified"))
      (node (ref "Q10") (pin "2") (pinfunction "B_2") (pintype "unspecified"))
      (node (ref "R30") (pin "2") (pinfunction "2_2") (pintype "unspecified"))
    )
    (net (code "26") (name "Net-(D11-K)") (class "Default")
      (node (ref "D11") (pin "2") (pinfunction "K_2") (pintype "unspecified"))
      (node (ref "Q11") (pin "2") (pinfunction "B_2") (pintype "unspecified"))
      (node (ref "R31") (pin "2") (pinfunction "2_2") (pintype "unspecified"))
    )
    (net (code "27") (name "Net-(D12-K)") (class "Default")
      (node (ref "D12") (pin "1") (pinfunction "K_1") (pintype "unspecified"))
      (node (ref "D13") (pin "2") (pinfunction "A_2") (pintype "unspecified"))
      (node (ref "S12") (pin "3") (pinfunction "1_3") (pintype "unspecified"))
    )
    (net (code "28") (name "Net-(D13-K)") (class "Default")
      (node (ref "D13") (pin "1") (pinfunction "K_1") (pintype "unspecified"))
      (node (ref "D14") (pin "1") (pinfunction "K_1") (pintype "unspecified"))
      (node (ref "R34") (pin "2") (pinfunction "2_2") (pintype "unspecified"))
    )
    (net (code "29") (name "Net-(D14-A)") (class "Default")
      (node (ref "D14") (pin "2") (pinfunction "A_2") (pintype "unspecified"))
      (node (ref "D15") (pin "1") (pinfunction "K_1") (pintype "unspecified"))
      (node (ref "S12") (pin "1") (pinfunction "3_1") (pintype "unspecified"))
    )
    (net (code "30") (name "Net-(D18-K)") (class "Default")
      (node (ref "D18") (pin "1") (pinfunction "K_1") (pintype "unspecified"))
      (node (ref "D19") (pin "2") (pinfunction "A_2") (pintype "unspecified"))
      (node (ref "S13") (pin "1") (pinfunction "3_1") (pintype "unspecified"))
    )
    (net (code "31") (name "Net-(D19-K)") (class "Default")
      (node (ref "D19") (pin "1") (pinfunction "K_1") (pintype "unspecified"))
      (node (ref "D20") (pin "1") (pinfunction "K_1") (pintype "unspecified"))
      (node (ref "R35") (pin "2") (pinfunction "2_2") (pintype "unspecified"))
    )
    (net (code "32") (name "Net-(D20-A)") (class "Default")
      (node (ref "D20") (pin "2") (pinfunction "A_2") (pintype "unspecified"))
      (node (ref "D21") (pin "1") (pinfunction "K_1") (pintype "unspecified"))
      (node (ref "S13") (pin "3") (pinfunction "1_3") (pintype "unspecified"))
    )
    (net (code "33") (name "Net-(D23-K)") (class "Default")
      (node (ref "D23") (pin "1") (pinfunction "K_1") (pintype "unspecified"))
      (node (ref "D24") (pin "2") (pinfunction "A_2") (pintype "unspecified"))
      (node (ref "S14") (pin "1") (pinfunction "3_1") (pintype "unspecified"))
    )
    (net (code "34") (name "Net-(D24-K)") (class "Default")
      (node (ref "D24") (pin "1") (pinfunction "K_1") (pintype "unspecified"))
      (node (ref "D25") (pin "1") (pinfunction "K_1") (pintype "unspecified"))
      (node (ref "R36") (pin "2") (pinfunction "2_2") (pintype "unspecified"))
    )
    (net (code "35") (name "Net-(D25-A)") (class "Default")
      (node (ref "D25") (pin "2") (pinfunction "A_2") (pintype "unspecified"))
      (node (ref "D26") (pin "1") (pinfunction "K_1") (pintype "unspecified"))
      (node (ref "S14") (pin "3") (pinfunction "1_3") (pintype "unspecified"))
    )
    (net (code "36") (name "Net-(D27-K)") (class "Default")
      (node (ref "D27") (pin "1") (pinfunction "K_1") (pintype "unspecified"))
      (node (ref "D28") (pin "2") (pinfunction "A_2") (pintype "unspecified"))
      (node (ref "S15") (pin "3") (pinfunction "1_3") (pintype "unspecified"))
    )
    (net (code "37") (name "Net-(D28-K)") (class "Default")
      (node (ref "D28") (pin "1") (pinfunction "K_1") (pintype "unspecified"))
      (node (ref "D29") (pin "1") (pinfunction "K_1") (pintype "unspecified"))
      (node (ref "R37") (pin "2") (pinfunction "2_2") (pintype "unspecified"))
    )
    (net (code "38") (name "Net-(D29-A)") (class "Default")
      (node (ref "D29") (pin "2") (pinfunction "A_2") (pintype "unspecified"))
      (node (ref "D30") (pin "1") (pinfunction "K_1") (pintype "unspecified"))
      (node (ref "S15") (pin "1") (pinfunction "3_1") (pintype "unspecified"))
    )
    (net (code "39") (name "Net-(D32-K)") (class "Default")
      (node (ref "D32") (pin "1") (pinfunction "K_1") (pintype "unspecified"))
      (node (ref "D33") (pin "2") (pinfunction "A_2") (pintype "unspecified"))
      (node (ref "S16") (pin "3") (pinfunction "1_3") (pintype "unspecified"))
    )
    (net (code "40") (name "Net-(D33-K)") (class "Default")
      (node (ref "D33") (pin "1") (pinfunction "K_1") (pintype "unspecified"))
      (node (ref "D34") (pin "1") (pinfunction "K_1") (pintype "unspecified"))
      (node (ref "R38") (pin "2") (pinfunction "2_2") (pintype "unspecified"))
    )
    (net (code "41") (name "Net-(D34-A)") (class "Default")
      (node (ref "D34") (pin "2") (pinfunction "A_2") (pintype "unspecified"))
      (node (ref "D35") (pin "1") (pinfunction "K_1") (pintype "unspecified"))
      (node (ref "S16") (pin "1") (pinfunction "3_1") (pintype "unspecified"))
    )
    (net (code "42") (name "Net-(D38-K)") (class "Default")
      (node (ref "D38") (pin "1") (pinfunction "K_1") (pintype "unspecified"))
      (node (ref "D39") (pin "2") (pinfunction "A_2") (pintype "unspecified"))
      (node (ref "S17") (pin "1") (pinfunction "3_1") (pintype "unspecified"))
    )
    (net (code "43") (name "Net-(D39-K)") (class "Default")
      (node (ref "D39") (pin "1") (pinfunction "K_1") (pintype "unspecified"))
      (node (ref "D40") (pin "1") (pinfunction "K_1") (pintype "unspecified"))
      (node (ref "R39") (pin "2") (pinfunction "2_2") (pintype "unspecified"))
    )
    (net (code "44") (name "Net-(D40-A)") (class "Default")
      (node (ref "D40") (pin "2") (pinfunction "A_2") (pintype "unspecified"))
      (node (ref "D41") (pin "1") (pinfunction "K_1") (pintype "unspecified"))
      (node (ref "S17") (pin "3") (pinfunction "1_3") (pintype "unspecified"))
    )
    (net (code "45") (name "Net-(LED1-Pad1)") (class "Default")
      (node (ref "LED1") (pin "1") (pinfunction "1_1") (pintype "unspecified"))
      (node (ref "R3") (pin "1") (pinfunction "1_1") (pintype "unspecified"))
    )
    (net (code "46") (name "Net-(LED2-Pad1)") (class "Default")
      (node (ref "LED2") (pin "1") (pinfunction "1_1") (pintype "unspecified"))
      (node (ref "R4") (pin "1") (pinfunction "1_1") (pintype "unspecified"))
    )
    (net (code "47") (name "Net-(LED3-Pad1)") (class "Default")
      (node (ref "LED3") (pin "1") (pinfunction "1_1") (pintype "unspecified"))
      (node (ref "R7") (pin "1") (pinfunction "1_1") (pintype "unspecified"))
    )
    (net (code "48") (name "Net-(LED4-Pad1)") (class "Default")
      (node (ref "LED4") (pin "1") (pinfunction "1_1") (pintype "unspecified"))
      (node (ref "R10") (pin "1") (pinfunction "1_1") (pintype "unspecified"))
    )
    (net (code "49") (name "Net-(LED5-Pad1)") (class "Default")
      (node (ref "LED5") (pin "1") (pinfunction "1_1") (pintype "unspecified"))
      (node (ref "R15") (pin "1") (pinfunction "1_1") (pintype "unspecified"))
    )
    (net (code "50") (name "Net-(LED6-Pad1)") (class "Default")
      (node (ref "LED6") (pin "1") (pinfunction "1_1") (pintype "unspecified"))
      (node (ref "R18") (pin "1") (pinfunction "1_1") (pintype "unspecified"))
    )
    (net (code "51") (name "Net-(LED7-Pad1)") (class "Default")
      (node (ref "LED7") (pin "1") (pinfunction "1_1") (pintype "unspecified"))
      (node (ref "R21") (pin "1") (pinfunction "1_1") (pintype "unspecified"))
    )
    (net (code "52") (name "Net-(LED8-Pad1)") (class "Default")
      (node (ref "LED8") (pin "1") (pinfunction "1_1") (pintype "unspecified"))
      (node (ref "R22") (pin "1") (pinfunction "1_1") (pintype "unspecified"))
    )
    (net (code "53") (name "Net-(LED9-Pad1)") (class "Default")
      (node (ref "LED9") (pin "1") (pinfunction "1_1") (pintype "unspecified"))
      (node (ref "R27") (pin "1") (pinfunction "1_1") (pintype "unspecified"))
    )
    (net (code "54") (name "Net-(LED10-Pad1)") (class "Default")
      (node (ref "LED10") (pin "1") (pinfunction "1_1") (pintype "unspecified"))
      (node (ref "R28") (pin "1") (pinfunction "1_1") (pintype "unspecified"))
    )
    (net (code "55") (name "Net-(LED11-Pad1)") (class "Default")
      (node (ref "LED11") (pin "1") (pinfunction "1_1") (pintype "unspecified"))
      (node (ref "R33") (pin "1") (pinfunction "1_1") (pintype "unspecified"))
    )
    (net (code "56") (name "Net-(LED12-Pad1)") (class "Default")
      (node (ref "LED12") (pin "1") (pinfunction "1_1") (pintype "unspecified"))
      (node (ref "R40") (pin "1") (pinfunction "1_1") (pintype "unspecified"))
    )
    (net (code "57") (name "Net-(LED13-Pad1)") (class "Default")
      (node (ref "LED13") (pin "1") (pinfunction "1_1") (pintype "unspecified"))
      (node (ref "R41") (pin "1") (pinfunction "1_1") (pintype "unspecified"))
    )
    (net (code "58") (name "Net-(LED14-Pad1)") (class "Default")
      (node (ref "LED14") (pin "1") (pinfunction "1_1") (pintype "unspecified"))
      (node (ref "R42") (pin "1") (pinfunction "1_1") (pintype "unspecified"))
    )
    (net (code "59") (name "Net-(LED15-Pad1)") (class "Default")
      (node (ref "LED15") (pin "1") (pinfunction "1_1") (pintype "unspecified"))
      (node (ref "R43") (pin "1") (pinfunction "1_1") (pintype "unspecified"))
    )
    (net (code "60") (name "Net-(LED16-Pad1)") (class "Default")
      (node (ref "LED16") (pin "1") (pinfunction "1_1") (pintype "unspecified"))
      (node (ref "R44") (pin "1") (pinfunction "1_1") (pintype "unspecified"))
    )
    (net (code "61") (name "Net-(LED17-Pad1)") (class "Default")
      (node (ref "LED17") (pin "1") (pinfunction "1_1") (pintype "unspecified"))
      (node (ref "R45") (pin "1") (pinfunction "1_1") (pintype "unspecified"))
    )
    (net (code "62") (name "Net-(R46-Pad2)") (class "Default")
      (node (ref "R46") (pin "2") (pinfunction "2_2") (pintype "unspecified"))
      (node (ref "U2") (pin "5") (pinfunction "5_5") (pintype "unspecified"))
    )
    (net (code "63") (name "Net-(R47-Pad2)") (class "Default")
      (node (ref "R47") (pin "2") (pinfunction "2_2") (pintype "unspecified"))
      (node (ref "U2") (pin "4") (pinfunction "4_4") (pintype "unspecified"))
    )
    (net (code "64") (name "Net-(S1-3)") (class "Default")
      (node (ref "R1") (pin "1") (pinfunction "1_1") (pintype "unspecified"))
      (node (ref "S1") (pin "1") (pinfunction "3_1") (pintype "unspecified"))
    )
    (net (code "65") (name "Net-(S2-3)") (class "Default")
      (node (ref "R6") (pin "1") (pinfunction "1_1") (pintype "unspecified"))
      (node (ref "S2") (pin "1") (pinfunction "3_1") (pintype "unspecified"))
    )
    (net (code "66") (name "Net-(S3-3)") (class "Default")
      (node (ref "R9") (pin "1") (pinfunction "1_1") (pintype "unspecified"))
      (node (ref "S3") (pin "1") (pinfunction "3_1") (pintype "unspecified"))
    )
    (net (code "67") (name "Net-(S4-3)") (class "Default")
      (node (ref "R12") (pin "1") (pinfunction "1_1") (pintype "unspecified"))
      (node (ref "S4") (pin "1") (pinfunction "3_1") (pintype "unspecified"))
    )
    (net (code "68") (name "Net-(S5-3)") (class "Default")
      (node (ref "R13") (pin "1") (pinfunction "1_1") (pintype "unspecified"))
      (node (ref "S5") (pin "1") (pinfunction "3_1") (pintype "unspecified"))
    )
    (net (code "69") (name "Net-(S6-3)") (class "Default")
      (node (ref "R16") (pin "1") (pinfunction "1_1") (pintype "unspecified"))
      (node (ref "S6") (pin "1") (pinfunction "3_1") (pintype "unspecified"))
    )
    (net (code "70") (name "Net-(S7-3)") (class "Default")
      (node (ref "R19") (pin "1") (pinfunction "1_1") (pintype "unspecified"))
      (node (ref "S7") (pin "1") (pinfunction "3_1") (pintype "unspecified"))
    )
    (net (code "71") (name "Net-(S8-3)") (class "Default")
      (node (ref "R24") (pin "1") (pinfunction "1_1") (pintype "unspecified"))
      (node (ref "S8") (pin "1") (pinfunction "3_1") (pintype "unspecified"))
    )
    (net (code "72") (name "Net-(S9-3)") (class "Default")
      (node (ref "R25") (pin "1") (pinfunction "1_1") (pintype "unspecified"))
      (node (ref "S9") (pin "1") (pinfunction "3_1") (pintype "unspecified"))
    )
    (net (code "73") (name "Net-(S10-3)") (class "Default")
      (node (ref "R30") (pin "1") (pinfunction "1_1") (pintype "unspecified"))
      (node (ref "S10") (pin "1") (pinfunction "3_1") (pintype "unspecified"))
    )
    (net (code "74") (name "Net-(S11-3)") (class "Default")
      (node (ref "R31") (pin "1") (pinfunction "1_1") (pintype "unspecified"))
      (node (ref "S11") (pin "1") (pinfunction "3_1") (pintype "unspecified"))
    )
    (net (code "75") (name "Net-(U1-TXD)") (class "Default")
      (node (ref "R46") (pin "1") (pinfunction "1_1") (pintype "unspecified"))
      (node (ref "U1") (pin "1") (pinfunction "TXD_1") (pintype "unspecified"))
    )
    (net (code "76") (name "Op Hat") (class "Default")
      (node (ref "Q7") (pin "3") (pinfunction "E_3") (pintype "unspecified"))
      (node (ref "R20") (pin "2") (pinfunction "2_2") (pintype "unspecified"))
      (node (ref "R21") (pin "2") (pinfunction "2_2") (pintype "unspecified"))
      (node (ref "U1") (pin "11") (pinfunction "D8_11") (pintype "unspecified"))
    )
    (net (code "77") (name "Snare") (class "Default")
      (node (ref "Q2") (pin "3") (pinfunction "E_3") (pintype "unspecified"))
      (node (ref "R4") (pin "2") (pinfunction "2_2") (pintype "unspecified"))
      (node (ref "R5") (pin "2") (pinfunction "2_2") (pintype "unspecified"))
      (node (ref "U1") (pin "7") (pinfunction "D4_7") (pintype "unspecified"))
    )
    (net (code "78") (name "Stutter Depth") (class "Default")
      (node (ref "D31") (pin "2") (pinfunction "K_2") (pintype "unspecified"))
      (node (ref "R37") (pin "1") (pinfunction "1_1") (pintype "unspecified"))
      (node (ref "R45") (pin "2") (pinfunction "2_2") (pintype "unspecified"))
      (node (ref "U1") (pin "24") (pinfunction "A5_24") (pintype "unspecified"))
    )
    (net (code "79") (name "Stutter Time") (class "Default")
      (node (ref "D36") (pin "2") (pinfunction "K_2") (pintype "unspecified"))
      (node (ref "R38") (pin "1") (pinfunction "1_1") (pintype "unspecified"))
      (node (ref "R44") (pin "2") (pinfunction "2_2") (pintype "unspecified"))
      (node (ref "U1") (pin "23") (pinfunction "A4_23") (pintype "unspecified"))
    )
    (net (code "80") (name "unconnected-(P15-Pad1)") (class "Default")
      (node (ref "P15") (pin "1") (pinfunction "1_1") (pintype "unspecified+no_connect"))
    )
    (net (code "81") (name "unconnected-(P15-Pad2)") (class "Default")
      (node (ref "P15") (pin "2") (pinfunction "2_2") (pintype "unspecified+no_connect"))
    )
    (net (code "82") (name "unconnected-(P15-Pad9)") (class "Default")
      (node (ref "P15") (pin "9") (pinfunction "9_9") (pintype "unspecified+no_connect"))
    )
    (net (code "83") (name "unconnected-(P15-Pad10)") (class "Default")
      (node (ref "P15") (pin "10") (pinfunction "10_10") (pintype "unspecified+no_connect"))
    )
    (net (code "84") (name "unconnected-(P15-Pad13)") (class "Default")
      (node (ref "P15") (pin "13") (pinfunction "13_13") (pintype "unspecified+no_connect"))
    )
    (net (code "85") (name "unconnected-(P15-Pad14)") (class "Default")
      (node (ref "P15") (pin "14") (pinfunction "14_14") (pintype "unspecified+no_connect"))
    )
    (net (code "86") (name "unconnected-(P15-Pad15)") (class "Default")
      (node (ref "P15") (pin "15") (pinfunction "15_15") (pintype "unspecified+no_connect"))
    )
    (net (code "87") (name "unconnected-(P15-Pad16)") (class "Default")
      (node (ref "P15") (pin "16") (pinfunction "16_16") (pintype "unspecified+no_connect"))
    )
    (net (code "88") (name "unconnected-(S1-Pad2)") (class "Default")
      (node (ref "S1") (pin "2") (pinfunction "2_2") (pintype "unspecified+no_connect"))
    )
    (net (code "89") (name "unconnected-(S2-Pad2)") (class "Default")
      (node (ref "S2") (pin "2") (pinfunction "2_2") (pintype "unspecified+no_connect"))
    )
    (net (code "90") (name "unconnected-(S3-Pad2)") (class "Default")
      (node (ref "S3") (pin "2") (pinfunction "2_2") (pintype "unspecified+no_connect"))
    )
    (net (code "91") (name "unconnected-(S4-Pad2)") (class "Default")
      (node (ref "S4") (pin "2") (pinfunction "2_2") (pintype "unspecified+no_connect"))
    )
    (net (code "92") (name "unconnected-(S5-Pad2)") (class "Default")
      (node (ref "S5") (pin "2") (pinfunction "2_2") (pintype "unspecified+no_connect"))
    )
    (net (code "93") (name "unconnected-(S6-Pad2)") (class "Default")
      (node (ref "S6") (pin "2") (pinfunction "2_2") (pintype "unspecified+no_connect"))
    )
    (net (code "94") (name "unconnected-(S7-Pad2)") (class "Default")
      (node (ref "S7") (pin "2") (pinfunction "2_2") (pintype "unspecified+no_connect"))
    )
    (net (code "95") (name "unconnected-(S8-Pad2)") (class "Default")
      (node (ref "S8") (pin "2") (pinfunction "2_2") (pintype "unspecified+no_connect"))
    )
    (net (code "96") (name "unconnected-(S9-Pad2)") (class "Default")
      (node (ref "S9") (pin "2") (pinfunction "2_2") (pintype "unspecified+no_connect"))
    )
    (net (code "97") (name "unconnected-(S10-Pad2)") (class "Default")
      (node (ref "S10") (pin "2") (pinfunction "2_2") (pintype "unspecified+no_connect"))
    )
    (net (code "98") (name "unconnected-(S11-Pad2)") (class "Default")
      (node (ref "S11") (pin "2") (pinfunction "2_2") (pintype "unspecified+no_connect"))
    )
    (net (code "99") (name "unconnected-(S12-Pad2)") (class "Default")
      (node (ref "S12") (pin "2") (pinfunction "2_2") (pintype "unspecified+no_connect"))
    )
    (net (code "100") (name "unconnected-(S13-Pad2)") (class "Default")
      (node (ref "S13") (pin "2") (pinfunction "2_2") (pintype "unspecified+no_connect"))
    )
    (net (code "101") (name "unconnected-(S14-Pad2)") (class "Default")
      (node (ref "S14") (pin "2") (pinfunction "2_2") (pintype "unspecified+no_connect"))
    )
    (net (code "102") (name "unconnected-(S15-Pad2)") (class "Default")
      (node (ref "S15") (pin "2") (pinfunction "2_2") (pintype "unspecified+no_connect"))
    )
    (net (code "103") (name "unconnected-(S16-Pad2)") (class "Default")
      (node (ref "S16") (pin "2") (pinfunction "2_2") (pintype "unspecified+no_connect"))
    )
    (net (code "104") (name "unconnected-(S17-Pad2)") (class "Default")
      (node (ref "S17") (pin "2") (pinfunction "2_2") (pintype "unspecified+no_connect"))
    )
    (net (code "105") (name "unconnected-(U1-3V3-Pad17)") (class "Default")
      (node (ref "U1") (pin "17") (pinfunction "3V3_17") (pintype "unspecified+no_connect"))
    )
    (net (code "106") (name "unconnected-(U1-A6-Pad25)") (class "Default")
      (node (ref "U1") (pin "25") (pinfunction "A6_25") (pintype "unspecified+no_connect"))
    )
    (net (code "107") (name "unconnected-(U1-A7-Pad26)") (class "Default")
      (node (ref "U1") (pin "26") (pinfunction "A7_26") (pintype "unspecified+no_connect"))
    )
    (net (code "108") (name "unconnected-(U1-D2-Pad5)") (class "Default")
      (node (ref "U1") (pin "5") (pinfunction "D2_5") (pintype "unspecified+no_connect"))
    )
    (net (code "109") (name "unconnected-(U1-GND-Pad4)") (class "Default")
      (node (ref "U1") (pin "4") (pinfunction "GND_4") (pintype "unspecified+no_connect"))
    )
    (net (code "110") (name "unconnected-(U1-REF-Pad18)") (class "Default")
      (node (ref "U1") (pin "18") (pinfunction "REF_18") (pintype "unspecified+no_connect"))
    )
    (net (code "111") (name "unconnected-(U1-RST-Pad3)") (class "Default")
      (node (ref "U1") (pin "3") (pinfunction "RST_3") (pintype "unspecified+no_connect"))
    )
    (net (code "112") (name "unconnected-(U1-RST-Pad28)") (class "Default")
      (node (ref "U1") (pin "28") (pinfunction "RST_28") (pintype "unspecified+no_connect"))
    )
    (net (code "113") (name "unconnected-(U1-RXD-Pad2)") (class "Default")
      (node (ref "U1") (pin "2") (pinfunction "RXD_2") (pintype "unspecified+no_connect"))
    )
    (net (code "114") (name "unconnected-(U1-Vin-Pad30)") (class "Default")
      (node (ref "U1") (pin "30") (pinfunction "Vin_30") (pintype "unspecified+no_connect"))
    )
    (net (code "115") (name "unconnected-(U2-Pad1)") (class "Default")
      (node (ref "U2") (pin "1") (pinfunction "1_1") (pintype "unspecified+no_connect"))
    )
    (net (code "116") (name "unconnected-(U2-Pad3)") (class "Default")
      (node (ref "U2") (pin "3") (pinfunction "3_3") (pintype "unspecified+no_connect"))
    )
  )
)
